# demeter_v25.net
KiCad netlist of a schematic drawn in EAGLE
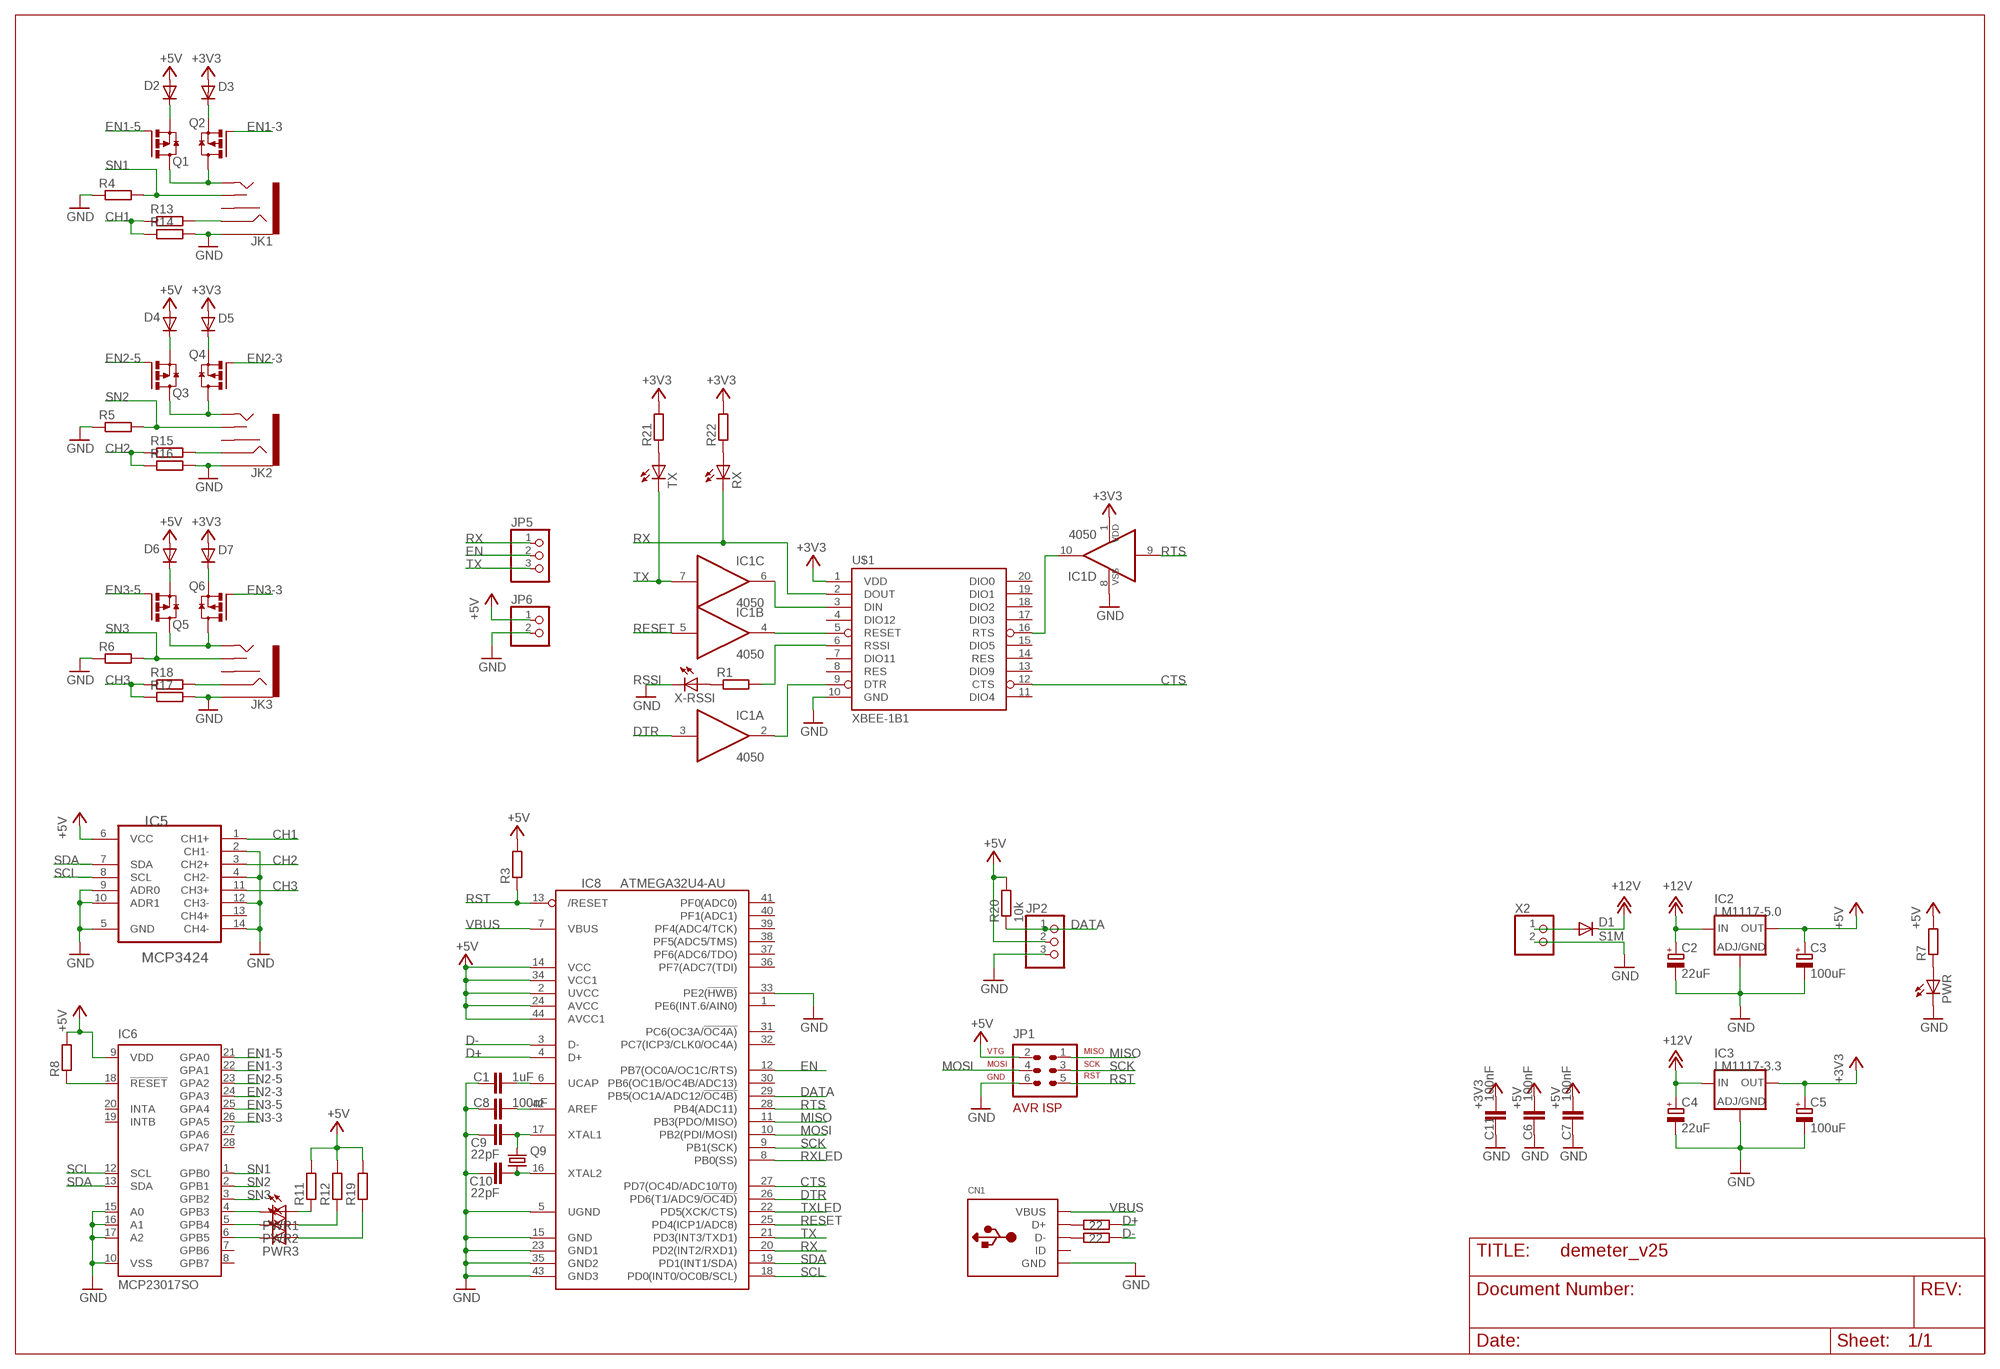
[diagram p0: schematic, sheet 1]

(export (version "E")
  (design (tool "Eeschema 10.0.6"))
  (components
    (comp (ref "C1")
      (value "1uF")
      (footprint "eagle-import:C0805K")
      (libsource (lib "eagle-import") (part "C-EUC0805K"))
    )
    (comp (ref "C2")
      (value "22uF")
      (footprint "eagle-import:PANASONIC_D")
      (libsource (lib "eagle-import") (part "CPOL-EUPD"))
    )
    (comp (ref "C3")
      (value "100uF")
      (footprint "eagle-import:PANASONIC_D")
      (libsource (lib "eagle-import") (part "CPOL-EUPD"))
    )
    (comp (ref "C4")
      (value "22uF")
      (footprint "eagle-import:PANASONIC_D")
      (libsource (lib "eagle-import") (part "CPOL-EUPD"))
    )
    (comp (ref "C5")
      (value "100uF")
      (footprint "eagle-import:PANASONIC_D")
      (libsource (lib "eagle-import") (part "CPOL-EUPD"))
    )
    (comp (ref "C6")
      (value "100nF")
      (footprint "eagle-import:C0805K")
      (libsource (lib "eagle-import") (part "C-EUC0805K"))
    )
    (comp (ref "C7")
      (value "100nF")
      (footprint "eagle-import:C0805K")
      (libsource (lib "eagle-import") (part "C-EUC0805K"))
    )
    (comp (ref "C8")
      (value "100nF")
      (footprint "eagle-import:C0805K")
      (libsource (lib "eagle-import") (part "C-EUC0805K"))
    )
    (comp (ref "C9")
      (value "22pF")
      (footprint "eagle-import:C0805K")
      (libsource (lib "eagle-import") (part "C-EUC0805K"))
    )
    (comp (ref "C10")
      (value "22pF")
      (footprint "eagle-import:C0805K")
      (libsource (lib "eagle-import") (part "C-EUC0805K"))
    )
    (comp (ref "C11")
      (value "100nF")
      (footprint "eagle-import:C0805K")
      (libsource (lib "eagle-import") (part "C-EUC0805K"))
    )
    (comp (ref "CN1")
      (value "USBMINIB")
      (footprint "eagle-import:USB-MINIB")
      (libsource (lib "eagle-import") (part "USBMINIB"))
    )
    (comp (ref "D1")
      (value "S1M")
      (footprint "eagle-import:DO-214AC")
      (libsource (lib "eagle-import") (part "S1M"))
    )
    (comp (ref "D2")
      (value "MBR0520")
      (footprint "eagle-import:SOD123")
      (libsource (lib "eagle-import") (part "MBR0520"))
    )
    (comp (ref "D3")
      (value "MBR0520")
      (footprint "eagle-import:SOD123")
      (libsource (lib "eagle-import") (part "MBR0520"))
    )
    (comp (ref "D4")
      (value "MBR0520")
      (footprint "eagle-import:SOD123")
      (libsource (lib "eagle-import") (part "MBR0520"))
    )
    (comp (ref "D5")
      (value "MBR0520")
      (footprint "eagle-import:SOD123")
      (libsource (lib "eagle-import") (part "MBR0520"))
    )
    (comp (ref "D6")
      (value "MBR0520")
      (footprint "eagle-import:SOD123")
      (libsource (lib "eagle-import") (part "MBR0520"))
    )
    (comp (ref "D7")
      (value "MBR0520")
      (footprint "eagle-import:SOD123")
      (libsource (lib "eagle-import") (part "MBR0520"))
    )
    (comp (ref "IC1")
      (value "4050")
      (footprint "eagle-import:SO16")
      (libsource (lib "eagle-import") (part "4050D"))
    )
    (comp (ref "IC2")
      (value "LM1117-5.0")
      (footprint "eagle-import:DPACK")
      (libsource (lib "eagle-import") (part "LM1117DT"))
    )
    (comp (ref "IC3")
      (value "LM1117-3.3")
      (footprint "eagle-import:DPACK")
      (libsource (lib "eagle-import") (part "LM1117DT"))
    )
    (comp (ref "IC5")
      (value "MCP3424")
      (footprint "eagle-import:SO14")
      (fields (field (name "MPN") "MCP3424-E/SL"))
      (libsource (lib "eagle-import") (part "MCP3424"))
    )
    (comp (ref "IC6")
      (value "MCP23017SO")
      (footprint "eagle-import:SO28W")
      (fields (field (name "MF") "MICROCHIP") (field (name "MPN") "MCP23017-E/SO"))
      (libsource (lib "eagle-import") (part "MCP23017SO"))
    )
    (comp (ref "IC8")
      (value "ATMEGA32U4-AU")
      (footprint "eagle-import:TQFP44")
      (libsource (lib "eagle-import") (part "ATMEGA32U4-AU"))
    )
    (comp (ref "JK1")
      (value "AUDIO-JACK2PTH")
      (footprint "eagle-import:AUDIO-JACK")
      (libsource (lib "eagle-import") (part "AUDIO-JACK2PTH"))
    )
    (comp (ref "JK2")
      (value "AUDIO-JACK2PTH")
      (footprint "eagle-import:AUDIO-JACK")
      (libsource (lib "eagle-import") (part "AUDIO-JACK2PTH"))
    )
    (comp (ref "JK3")
      (value "AUDIO-JACK2PTH")
      (footprint "eagle-import:AUDIO-JACK")
      (libsource (lib "eagle-import") (part "AUDIO-JACK2PTH"))
    )
    (comp (ref "JP1")
      (value "AVR-ISP-6")
      (footprint "eagle-import:AVR-ISP-6")
      (libsource (lib "eagle-import") (part "AVR-ISP-6"))
    )
    (comp (ref "JP2")
      (value "PINHD-1X3180")
      (footprint "eagle-import:1X03")
      (libsource (lib "eagle-import") (part "PINHD-1X3180"))
    )
    (comp (ref "JP5")
      (value "PINHD-1X3180")
      (footprint "eagle-import:1X03")
      (libsource (lib "eagle-import") (part "PINHD-1X3180"))
    )
    (comp (ref "JP6")
      (value "PINHD-1X2")
      (footprint "eagle-import:1X02")
      (libsource (lib "eagle-import") (part "PINHD-1X2"))
    )
    (comp (ref "PWR")
      (value "LED0805")
      (footprint "eagle-import:CHIP-LED0805")
      (libsource (lib "eagle-import") (part "LED0805"))
    )
    (comp (ref "PWR1")
      (value "LED0805")
      (footprint "eagle-import:CHIP-LED0805")
      (libsource (lib "eagle-import") (part "LED0805"))
    )
    (comp (ref "PWR2")
      (value "LED0805")
      (footprint "eagle-import:CHIP-LED0805")
      (libsource (lib "eagle-import") (part "LED0805"))
    )
    (comp (ref "PWR3")
      (value "LED0805")
      (footprint "eagle-import:CHIP-LED0805")
      (libsource (lib "eagle-import") (part "LED0805"))
    )
    (comp (ref "Q1")
      (value "IRLML6402")
      (footprint "eagle-import:SOT23")
      (libsource (lib "eagle-import") (part "IRLML6402"))
    )
    (comp (ref "Q2")
      (value "IRLML6402")
      (footprint "eagle-import:SOT23")
      (libsource (lib "eagle-import") (part "IRLML6402"))
    )
    (comp (ref "Q3")
      (value "IRLML6402")
      (footprint "eagle-import:SOT23")
      (libsource (lib "eagle-import") (part "IRLML6402"))
    )
    (comp (ref "Q4")
      (value "IRLML6402")
      (footprint "eagle-import:SOT23")
      (libsource (lib "eagle-import") (part "IRLML6402"))
    )
    (comp (ref "Q5")
      (value "IRLML6402")
      (footprint "eagle-import:SOT23")
      (libsource (lib "eagle-import") (part "IRLML6402"))
    )
    (comp (ref "Q6")
      (value "IRLML6402")
      (footprint "eagle-import:SOT23")
      (libsource (lib "eagle-import") (part "IRLML6402"))
    )
    (comp (ref "Q9")
      (value "CRYSTALHC49UP")
      (footprint "eagle-import:HC49UP")
      (libsource (lib "eagle-import") (part "CRYSTALHC49UP"))
    )
    (comp (ref "R1")
      (value "R-EU_R0805")
      (footprint "eagle-import:R0805")
      (libsource (lib "eagle-import") (part "R-EU_R0805"))
    )
    (comp (ref "R3")
      (value "R-EU_R0805")
      (footprint "eagle-import:R0805")
      (libsource (lib "eagle-import") (part "R-EU_R0805"))
    )
    (comp (ref "R4")
      (value "R-EU_R0805")
      (footprint "eagle-import:R0805")
      (libsource (lib "eagle-import") (part "R-EU_R0805"))
    )
    (comp (ref "R5")
      (value "R-EU_R0805")
      (footprint "eagle-import:R0805")
      (libsource (lib "eagle-import") (part "R-EU_R0805"))
    )
    (comp (ref "R6")
      (value "R-EU_R0805")
      (footprint "eagle-import:R0805")
      (libsource (lib "eagle-import") (part "R-EU_R0805"))
    )
    (comp (ref "R7")
      (value "R-EU_R0805")
      (footprint "eagle-import:R0805")
      (libsource (lib "eagle-import") (part "R-EU_R0805"))
    )
    (comp (ref "R8")
      (value "R-EU_R0805")
      (footprint "eagle-import:R0805")
      (libsource (lib "eagle-import") (part "R-EU_R0805"))
    )
    (comp (ref "R9")
      (value "22")
      (footprint "eagle-import:R0805")
      (libsource (lib "eagle-import") (part "R-EU_R0805"))
    )
    (comp (ref "R10")
      (value "22")
      (footprint "eagle-import:R0805")
      (libsource (lib "eagle-import") (part "R-EU_R0805"))
    )
    (comp (ref "R11")
      (value "R-EU_R0805")
      (footprint "eagle-import:R0805")
      (libsource (lib "eagle-import") (part "R-EU_R0805"))
    )
    (comp (ref "R12")
      (value "R-EU_R0805")
      (footprint "eagle-import:R0805")
      (libsource (lib "eagle-import") (part "R-EU_R0805"))
    )
    (comp (ref "R13")
      (value "R-EU_R0805")
      (footprint "eagle-import:R0805")
      (libsource (lib "eagle-import") (part "R-EU_R0805"))
    )
    (comp (ref "R14")
      (value "R-EU_R0805")
      (footprint "eagle-import:R0805")
      (libsource (lib "eagle-import") (part "R-EU_R0805"))
    )
    (comp (ref "R15")
      (value "R-EU_R0805")
      (footprint "eagle-import:R0805")
      (libsource (lib "eagle-import") (part "R-EU_R0805"))
    )
    (comp (ref "R16")
      (value "R-EU_R0805")
      (footprint "eagle-import:R0805")
      (libsource (lib "eagle-import") (part "R-EU_R0805"))
    )
    (comp (ref "R17")
      (value "R-EU_R0805")
      (footprint "eagle-import:R0805")
      (libsource (lib "eagle-import") (part "R-EU_R0805"))
    )
    (comp (ref "R18")
      (value "R-EU_R0805")
      (footprint "eagle-import:R0805")
      (libsource (lib "eagle-import") (part "R-EU_R0805"))
    )
    (comp (ref "R19")
      (value "R-EU_R0805")
      (footprint "eagle-import:R0805")
      (libsource (lib "eagle-import") (part "R-EU_R0805"))
    )
    (comp (ref "R20")
      (value "10k")
      (footprint "eagle-import:R0805")
      (libsource (lib "eagle-import") (part "R-EU_R0805"))
    )
    (comp (ref "R21")
      (value "R-EU_R0805")
      (footprint "eagle-import:R0805")
      (libsource (lib "eagle-import") (part "R-EU_R0805"))
    )
    (comp (ref "R22")
      (value "R-EU_R0805")
      (footprint "eagle-import:R0805")
      (libsource (lib "eagle-import") (part "R-EU_R0805"))
    )
    (comp (ref "RX")
      (value "LED0805")
      (footprint "eagle-import:CHIP-LED0805")
      (libsource (lib "eagle-import") (part "LED0805"))
    )
    (comp (ref "TX")
      (value "LED0805")
      (footprint "eagle-import:CHIP-LED0805")
      (libsource (lib "eagle-import") (part "LED0805"))
    )
    (comp (ref "U$1")
      (value "XBEE-1B1")
      (footprint "eagle-import:XBEE-1")
      (libsource (lib "eagle-import") (part "XBEE-1B1"))
    )
    (comp (ref "X-RSSI")
      (value "LED0805")
      (footprint "eagle-import:CHIP-LED0805")
      (libsource (lib "eagle-import") (part "LED0805"))
    )
    (comp (ref "X2")
      (value "W237-102")
      (footprint "eagle-import:W237-102")
      (libsource (lib "eagle-import") (part "W237-102"))
    )
  )
  (nets
    (net (code "1") (name "+3V3") (class "Default")
      (node (ref "C11") (pin "1") (pinfunction "1_1") (pintype "passive"))
      (node (ref "C5") (pin "+") (pinfunction "+_+") (pintype "passive"))
      (node (ref "D3") (pin "A") (pinfunction "A_A") (pintype "passive"))
      (node (ref "D5") (pin "A") (pinfunction "A_A") (pintype "passive"))
      (node (ref "D7") (pin "A") (pinfunction "A_A") (pintype "passive"))
      (node (ref "IC1") (pin "1") (pinfunction "VDD_1") (pintype "power_in"))
      (node (ref "IC3") (pin "4") (pinfunction "OUT_4") (pintype "passive"))
      (node (ref "R21") (pin "2") (pinfunction "2_2") (pintype "passive"))
      (node (ref "R22") (pin "2") (pinfunction "2_2") (pintype "passive"))
      (node (ref "U$1") (pin "1") (pinfunction "VDD_1") (pintype "power_in"))
    )
    (net (code "2") (name "+5V") (class "Default")
      (node (ref "C3") (pin "+") (pinfunction "+_+") (pintype "passive"))
      (node (ref "C6") (pin "1") (pinfunction "1_1") (pintype "passive"))
      (node (ref "C7") (pin "1") (pinfunction "1_1") (pintype "passive"))
      (node (ref "D2") (pin "A") (pinfunction "A_A") (pintype "passive"))
      (node (ref "D4") (pin "A") (pinfunction "A_A") (pintype "passive"))
      (node (ref "D6") (pin "A") (pinfunction "A_A") (pintype "passive"))
      (node (ref "IC2") (pin "4") (pinfunction "OUT_4") (pintype "passive"))
      (node (ref "IC5") (pin "6") (pinfunction "VCC_6") (pintype "power_in"))
      (node (ref "IC6") (pin "9") (pinfunction "VDD_9") (pintype "power_in"))
      (node (ref "IC8") (pin "14") (pinfunction "VCC_14") (pintype "bidirectional"))
      (node (ref "IC8") (pin "2") (pinfunction "UVCC_2") (pintype "bidirectional"))
      (node (ref "IC8") (pin "24") (pinfunction "AVCC_24") (pintype "bidirectional"))
      (node (ref "IC8") (pin "34") (pinfunction "VCC1_34") (pintype "bidirectional"))
      (node (ref "IC8") (pin "44") (pinfunction "AVCC1_44") (pintype "bidirectional"))
      (node (ref "JP1") (pin "2") (pinfunction "VTG_2") (pintype "passive"))
      (node (ref "JP2") (pin "2") (pinfunction "2_2") (pintype "passive"))
      (node (ref "JP6") (pin "1") (pinfunction "1_1") (pintype "passive"))
      (node (ref "R11") (pin "2") (pinfunction "2_2") (pintype "passive"))
      (node (ref "R12") (pin "2") (pinfunction "2_2") (pintype "passive"))
      (node (ref "R19") (pin "2") (pinfunction "2_2") (pintype "passive"))
      (node (ref "R20") (pin "2") (pinfunction "2_2") (pintype "passive"))
      (node (ref "R3") (pin "2") (pinfunction "2_2") (pintype "passive"))
      (node (ref "R7") (pin "2") (pinfunction "2_2") (pintype "passive"))
      (node (ref "R8") (pin "2") (pinfunction "2_2") (pintype "passive"))
    )
    (net (code "3") (name "+12V") (class "Default")
      (node (ref "C2") (pin "+") (pinfunction "+_+") (pintype "passive"))
      (node (ref "C4") (pin "+") (pinfunction "+_+") (pintype "passive"))
      (node (ref "D1") (pin "C") (pinfunction "C_C") (pintype "passive"))
      (node (ref "IC2") (pin "3") (pinfunction "IN_3") (pintype "input"))
      (node (ref "IC3") (pin "3") (pinfunction "IN_3") (pintype "input"))
    )
    (net (code "4") (name "/CH1") (class "Default")
      (node (ref "IC5") (pin "1") (pinfunction "CH1+_1") (pintype "input"))
      (node (ref "R13") (pin "1") (pinfunction "1_1") (pintype "passive"))
      (node (ref "R14") (pin "1") (pinfunction "1_1") (pintype "passive"))
    )
    (net (code "5") (name "/CH2") (class "Default")
      (node (ref "IC5") (pin "3") (pinfunction "CH2+_3") (pintype "input"))
      (node (ref "R15") (pin "1") (pinfunction "1_1") (pintype "passive"))
      (node (ref "R16") (pin "1") (pinfunction "1_1") (pintype "passive"))
    )
    (net (code "6") (name "/CH3") (class "Default")
      (node (ref "IC5") (pin "11") (pinfunction "CH3+_11") (pintype "input"))
      (node (ref "R17") (pin "1") (pinfunction "1_1") (pintype "passive"))
      (node (ref "R18") (pin "1") (pinfunction "1_1") (pintype "passive"))
    )
    (net (code "7") (name "/CTS") (class "Default")
      (node (ref "IC8") (pin "27") (pinfunction "PD7(OC4D/ADC10/T0)_27") (pintype "bidirectional"))
      (node (ref "U$1") (pin "12") (pinfunction "CTS_12") (pintype "output"))
    )
    (net (code "8") (name "/D+") (class "Default")
      (node (ref "IC8") (pin "4") (pinfunction "D+_4") (pintype "bidirectional"))
      (node (ref "R9") (pin "1") (pinfunction "1_1") (pintype "passive"))
    )
    (net (code "9") (name "/D-") (class "Default")
      (node (ref "IC8") (pin "3") (pinfunction "D-_3") (pintype "bidirectional"))
      (node (ref "R10") (pin "1") (pinfunction "1_1") (pintype "passive"))
    )
    (net (code "10") (name "/DATA") (class "Default")
      (node (ref "IC8") (pin "29") (pinfunction "PB5(OC1A/ADC12/~{OC4B})_29") (pintype "bidirectional"))
      (node (ref "JP2") (pin "1") (pinfunction "1_1") (pintype "passive"))
      (node (ref "R20") (pin "1") (pinfunction "1_1") (pintype "passive"))
    )
    (net (code "11") (name "/DTR") (class "Default")
      (node (ref "IC1") (pin "3") (pinfunction "I_3") (pintype "input"))
      (node (ref "IC8") (pin "26") (pinfunction "PD6(T1/ADC9/~{OC4D})_26") (pintype "bidirectional"))
    )
    (net (code "12") (name "/EN") (class "Default")
      (node (ref "IC8") (pin "12") (pinfunction "PB7(OC0A/OC1C/RTS)_12") (pintype "bidirectional"))
      (node (ref "JP5") (pin "2") (pinfunction "2_2") (pintype "passive"))
    )
    (net (code "13") (name "/EN1-3") (class "Default")
      (node (ref "IC6") (pin "22") (pinfunction "GPA1_22") (pintype "bidirectional"))
      (node (ref "Q2") (pin "1") (pinfunction "G_1") (pintype "passive"))
    )
    (net (code "14") (name "/EN1-5") (class "Default")
      (node (ref "IC6") (pin "21") (pinfunction "GPA0_21") (pintype "bidirectional"))
      (node (ref "Q1") (pin "1") (pinfunction "G_1") (pintype "passive"))
    )
    (net (code "15") (name "/EN2-3") (class "Default")
      (node (ref "IC6") (pin "24") (pinfunction "GPA3_24") (pintype "bidirectional"))
      (node (ref "Q4") (pin "1") (pinfunction "G_1") (pintype "passive"))
    )
    (net (code "16") (name "/EN2-5") (class "Default")
      (node (ref "IC6") (pin "23") (pinfunction "GPA2_23") (pintype "bidirectional"))
      (node (ref "Q3") (pin "1") (pinfunction "G_1") (pintype "passive"))
    )
    (net (code "17") (name "/EN3-3") (class "Default")
      (node (ref "IC6") (pin "26") (pinfunction "GPA5_26") (pintype "bidirectional"))
      (node (ref "Q6") (pin "1") (pinfunction "G_1") (pintype "passive"))
    )
    (net (code "18") (name "/EN3-5") (class "Default")
      (node (ref "IC6") (pin "25") (pinfunction "GPA4_25") (pintype "bidirectional"))
      (node (ref "Q5") (pin "1") (pinfunction "G_1") (pintype "passive"))
    )
    (net (code "19") (name "/MISO") (class "Default")
      (node (ref "IC8") (pin "11") (pinfunction "PB3(PDO/MISO)_11") (pintype "bidirectional"))
      (node (ref "JP1") (pin "1") (pinfunction "MISO_1") (pintype "passive"))
    )
    (net (code "20") (name "/MOSI") (class "Default")
      (node (ref "IC8") (pin "10") (pinfunction "PB2(PDI/MOSI)_10") (pintype "bidirectional"))
      (node (ref "JP1") (pin "4") (pinfunction "MOSI_4") (pintype "passive"))
    )
    (net (code "21") (name "/RESET") (class "Default")
      (node (ref "IC1") (pin "5") (pinfunction "I_5") (pintype "input"))
      (node (ref "IC8") (pin "25") (pinfunction "PD4(ICP1/ADC8)_25") (pintype "bidirectional"))
    )
    (net (code "22") (name "/RSSI") (class "Default")
      (node (ref "R1") (pin "2") (pinfunction "2_2") (pintype "passive"))
      (node (ref "U$1") (pin "6") (pinfunction "RSSI_6") (pintype "bidirectional"))
    )
    (net (code "23") (name "/RST") (class "Default")
      (node (ref "IC8") (pin "13") (pinfunction "/RESET_13") (pintype "bidirectional"))
      (node (ref "JP1") (pin "5") (pinfunction "RST_5") (pintype "passive"))
      (node (ref "R3") (pin "1") (pinfunction "1_1") (pintype "passive"))
    )
    (net (code "24") (name "/RTS") (class "Default")
      (node (ref "IC1") (pin "9") (pinfunction "I_9") (pintype "input"))
      (node (ref "IC8") (pin "28") (pinfunction "PB4(ADC11)_28") (pintype "bidirectional"))
    )
    (net (code "25") (name "/RX") (class "Default")
      (node (ref "IC8") (pin "20") (pinfunction "PD2(INT2/RXD1)_20") (pintype "bidirectional"))
      (node (ref "JP5") (pin "1") (pinfunction "1_1") (pintype "passive"))
      (node (ref "RX") (pin "C") (pinfunction "C_C") (pintype "passive"))
      (node (ref "U$1") (pin "2") (pinfunction "DOUT_2") (pintype "output"))
    )
    (net (code "26") (name "/RXLED") (class "Default")
      (node (ref "IC8") (pin "8") (pinfunction "PB0(SS)_8") (pintype "bidirectional"))
    )
    (net (code "27") (name "/SCK") (class "Default")
      (node (ref "IC8") (pin "9") (pinfunction "PB1(SCK)_9") (pintype "bidirectional"))
      (node (ref "JP1") (pin "3") (pinfunction "SCK_3") (pintype "passive"))
    )
    (net (code "28") (name "/SCL") (class "Default")
      (node (ref "IC5") (pin "8") (pinfunction "SCL_8") (pintype "input"))
      (node (ref "IC6") (pin "12") (pinfunction "SCL_12") (pintype "input"))
      (node (ref "IC8") (pin "18") (pinfunction "PD0(INT0/OC0B/SCL)_18") (pintype "bidirectional"))
    )
    (net (code "29") (name "/SDA") (class "Default")
      (node (ref "IC5") (pin "7") (pinfunction "SDA_7") (pintype "bidirectional"))
      (node (ref "IC6") (pin "13") (pinfunction "SDA_13") (pintype "bidirectional"))
      (node (ref "IC8") (pin "19") (pinfunction "PD1(INT1/SDA)_19") (pintype "bidirectional"))
    )
    (net (code "30") (name "/SN1") (class "Default")
      (node (ref "IC6") (pin "1") (pinfunction "GPB0_1") (pintype "bidirectional"))
      (node (ref "JK1") (pin "TSH") (pinfunction "TSH_TSH") (pintype "bidirectional"))
      (node (ref "R4") (pin "2") (pinfunction "2_2") (pintype "passive"))
    )
    (net (code "31") (name "/SN2") (class "Default")
      (node (ref "IC6") (pin "2") (pinfunction "GPB1_2") (pintype "bidirectional"))
      (node (ref "JK2") (pin "TSH") (pinfunction "TSH_TSH") (pintype "bidirectional"))
      (node (ref "R5") (pin "2") (pinfunction "2_2") (pintype "passive"))
    )
    (net (code "32") (name "/SN3") (class "Default")
      (node (ref "IC6") (pin "3") (pinfunction "GPB2_3") (pintype "bidirectional"))
      (node (ref "JK3") (pin "TSH") (pinfunction "TSH_TSH") (pintype "bidirectional"))
      (node (ref "R6") (pin "2") (pinfunction "2_2") (pintype "passive"))
    )
    (net (code "33") (name "/TX") (class "Default")
      (node (ref "IC1") (pin "7") (pinfunction "I_7") (pintype "input"))
      (node (ref "IC8") (pin "21") (pinfunction "PD3(INT3/TXD1)_21") (pintype "bidirectional"))
      (node (ref "JP5") (pin "3") (pinfunction "3_3") (pintype "passive"))
      (node (ref "TX") (pin "C") (pinfunction "C_C") (pintype "passive"))
    )
    (net (code "34") (name "/TXLED") (class "Default")
      (node (ref "IC8") (pin "22") (pinfunction "PD5(XCK/CTS)_22") (pintype "bidirectional"))
    )
    (net (code "35") (name "/VBUS") (class "Default")
      (node (ref "CN1") (pin "VBUS") (pinfunction "VBUS_VBUS") (pintype "power_in"))
      (node (ref "IC8") (pin "7") (pinfunction "VBUS_7") (pintype "bidirectional"))
    )
    (net (code "36") (name "GND") (class "Default")
      (node (ref "C1") (pin "2") (pinfunction "2_2") (pintype "passive"))
      (node (ref "C10") (pin "2") (pinfunction "2_2") (pintype "passive"))
      (node (ref "C11") (pin "2") (pinfunction "2_2") (pintype "passive"))
      (node (ref "C2") (pin "-") (pinfunction "-_-") (pintype "passive"))
      (node (ref "C3") (pin "-") (pinfunction "-_-") (pintype "passive"))
      (node (ref "C4") (pin "-") (pinfunction "-_-") (pintype "passive"))
      (node (ref "C5") (pin "-") (pinfunction "-_-") (pintype "passive"))
      (node (ref "C6") (pin "2") (pinfunction "2_2") (pintype "passive"))
      (node (ref "C7") (pin "2") (pinfunction "2_2") (pintype "passive"))
      (node (ref "C8") (pin "2") (pinfunction "2_2") (pintype "passive"))
      (node (ref "C9") (pin "2") (pinfunction "2_2") (pintype "passive"))
      (node (ref "CN1") (pin "GND") (pinfunction "GND_GND") (pintype "power_in"))
      (node (ref "IC1") (pin "8") (pinfunction "VSS_8") (pintype "power_in"))
      (node (ref "IC2") (pin "1") (pinfunction "ADJ_1") (pintype "input"))
      (node (ref "IC3") (pin "1") (pinfunction "ADJ_1") (pintype "input"))
      (node (ref "IC5") (pin "10") (pinfunction "ADR1_10") (pintype "input"))
      (node (ref "IC5") (pin "12") (pinfunction "CH3-_12") (pintype "input"))
      (node (ref "IC5") (pin "14") (pinfunction "CH4-_14") (pintype "input"))
      (node (ref "IC5") (pin "2") (pinfunction "CH1-_2") (pintype "input"))
      (node (ref "IC5") (pin "4") (pinfunction "CH2-_4") (pintype "input"))
      (node (ref "IC5") (pin "5") (pinfunction "GND_5") (pintype "power_in"))
      (node (ref "IC5") (pin "9") (pinfunction "ADR0_9") (pintype "input"))
      (node (ref "IC6") (pin "10") (pinfunction "VSS_10") (pintype "power_in"))
      (node (ref "IC6") (pin "15") (pinfunction "A0_15") (pintype "input"))
      (node (ref "IC6") (pin "16") (pinfunction "A1_16") (pintype "input"))
      (node (ref "IC6") (pin "17") (pinfunction "A2_17") (pintype "input"))
      (node (ref "IC8") (pin "15") (pinfunction "GND_15") (pintype "bidirectional"))
      (node (ref "IC8") (pin "23") (pinfunction "GND1_23") (pintype "bidirectional"))
      (node (ref "IC8") (pin "33") (pinfunction "PE2(~{HWB})_33") (pintype "bidirectional"))
      (node (ref "IC8") (pin "35") (pinfunction "GND2_35") (pintype "bidirectional"))
      (node (ref "IC8") (pin "43") (pinfunction "GND3_43") (pintype "bidirectional"))
      (node (ref "IC8") (pin "5") (pinfunction "UGND_5") (pintype "bidirectional"))
      (node (ref "JK1") (pin "SLEEVE") (pinfunction "SLEEVE_SLEEVE") (pintype "bidirectional"))
      (node (ref "JK2") (pin "SLEEVE") (pinfunction "SLEEVE_SLEEVE") (pintype "bidirectional"))
      (node (ref "JK3") (pin "SLEEVE") (pinfunction "SLEEVE_SLEEVE") (pintype "bidirectional"))
      (node (ref "JP1") (pin "6") (pinfunction "GND_6") (pintype "passive"))
      (node (ref "JP2") (pin "3") (pinfunction "3_3") (pintype "passive"))
      (node (ref "JP6") (pin "2") (pinfunction "2_2") (pintype "passive"))
      (node (ref "PWR") (pin "C") (pinfunction "C_C") (pintype "passive"))
      (node (ref "R14") (pin "2") (pinfunction "2_2") (pintype "passive"))
      (node (ref "R16") (pin "2") (pinfunction "2_2") (pintype "passive"))
      (node (ref "R17") (pin "2") (pinfunction "2_2") (pintype "passive"))
      (node (ref "R4") (pin "1") (pinfunction "1_1") (pintype "passive"))
      (node (ref "R5") (pin "1") (pinfunction "1_1") (pintype "passive"))
      (node (ref "R6") (pin "1") (pinfunction "1_1") (pintype "passive"))
      (node (ref "U$1") (pin "10") (pinfunction "GND_10") (pintype "power_in"))
      (node (ref "X-RSSI") (pin "C") (pinfunction "C_C") (pintype "passive"))
      (node (ref "X2") (pin "2") (pinfunction "2_2") (pintype "passive"))
    )
    (net (code "37") (name "Net-(CN1-PadD+)") (class "Default")
      (node (ref "CN1") (pin "D+") (pinfunction "D+_D+") (pintype "bidirectional"))
      (node (ref "R9") (pin "2") (pinfunction "2_2") (pintype "passive"))
    )
    (net (code "38") (name "Net-(CN1-PadD-)") (class "Default")
      (node (ref "CN1") (pin "D-") (pinfunction "D-_D-") (pintype "bidirectional"))
      (node (ref "R10") (pin "2") (pinfunction "2_2") (pintype "passive"))
    )
    (net (code "39") (name "Net-(D1-PadA)") (class "Default")
      (node (ref "D1") (pin "A") (pinfunction "A_A") (pintype "passive"))
      (node (ref "X2") (pin "1") (pinfunction "1_1") (pintype "passive"))
    )
    (net (code "40") (name "Net-(IC1A-O)") (class "Default")
      (node (ref "IC1") (pin "2") (pinfunction "O_2") (pintype "output"))
      (node (ref "U$1") (pin "9") (pinfunction "DTR_9") (pintype "bidirectional"))
    )
    (net (code "41") (name "Net-(IC1B-O)") (class "Default")
      (node (ref "IC1") (pin "4") (pinfunction "O_4") (pintype "output"))
      (node (ref "U$1") (pin "5") (pinfunction "RESET_5") (pintype "input"))
    )
    (net (code "42") (name "Net-(IC1C-O)") (class "Default")
      (node (ref "IC1") (pin "6") (pinfunction "O_6") (pintype "output"))
      (node (ref "U$1") (pin "3") (pinfunction "DIN_3") (pintype "input"))
    )
    (net (code "43") (name "Net-(IC1D-O)") (class "Default")
      (node (ref "IC1") (pin "10") (pinfunction "O_10") (pintype "output"))
      (node (ref "U$1") (pin "16") (pinfunction "RTS_16") (pintype "input"))
    )
    (net (code "44") (name "Net-(IC6-GPB3)") (class "Default")
      (node (ref "IC6") (pin "4") (pinfunction "GPB3_4") (pintype "bidirectional"))
      (node (ref "PWR1") (pin "C") (pinfunction "C_C") (pintype "passive"))
    )
    (net (code "45") (name "Net-(IC6-GPB4)") (class "Default")
      (node (ref "IC6") (pin "5") (pinfunction "GPB4_5") (pintype "bidirectional"))
      (node (ref "PWR2") (pin "C") (pinfunction "C_C") (pintype "passive"))
    )
    (net (code "46") (name "Net-(IC6-GPB5)") (class "Default")
      (node (ref "IC6") (pin "6") (pinfunction "GPB5_6") (pintype "bidirectional"))
      (node (ref "PWR3") (pin "C") (pinfunction "C_C") (pintype "passive"))
    )
    (net (code "47") (name "Net-(IC6-~{RESET})") (class "Default")
      (node (ref "IC6") (pin "18") (pinfunction "~{RESET}_18") (pintype "input"))
      (node (ref "R8") (pin "1") (pinfunction "1_1") (pintype "passive"))
    )
    (net (code "48") (name "Net-(IC8-AREF)") (class "Default")
      (node (ref "C8") (pin "1") (pinfunction "1_1") (pintype "passive"))
      (node (ref "IC8") (pin "42") (pinfunction "AREF_42") (pintype "bidirectional"))
    )
    (net (code "49") (name "Net-(IC8-UCAP)") (class "Default")
      (node (ref "C1") (pin "1") (pinfunction "1_1") (pintype "passive"))
      (node (ref "IC8") (pin "6") (pinfunction "UCAP_6") (pintype "bidirectional"))
    )
    (net (code "50") (name "Net-(IC8-XTAL1)") (class "Default")
      (node (ref "C9") (pin "1") (pinfunction "1_1") (pintype "passive"))
      (node (ref "IC8") (pin "17") (pinfunction "XTAL1_17") (pintype "bidirectional"))
      (node (ref "Q9") (pin "2") (pinfunction "2_2") (pintype "passive"))
    )
    (net (code "51") (name "Net-(IC8-XTAL2)") (class "Default")
      (node (ref "C10") (pin "1") (pinfunction "1_1") (pintype "passive"))
      (node (ref "IC8") (pin "16") (pinfunction "XTAL2_16") (pintype "bidirectional"))
      (node (ref "Q9") (pin "1") (pinfunction "1_1") (pintype "passive"))
    )
    (net (code "52") (name "Net-(JK1-PadRING)") (class "Default")
      (node (ref "JK1") (pin "RING") (pinfunction "RING_RING") (pintype "bidirectional"))
      (node (ref "R13") (pin "2") (pinfunction "2_2") (pintype "passive"))
    )
    (net (code "53") (name "Net-(JK2-PadRING)") (class "Default")
      (node (ref "JK2") (pin "RING") (pinfunction "RING_RING") (pintype "bidirectional"))
      (node (ref "R15") (pin "2") (pinfunction "2_2") (pintype "passive"))
    )
    (net (code "54") (name "Net-(JK3-PadRING)") (class "Default")
      (node (ref "JK3") (pin "RING") (pinfunction "RING_RING") (pintype "bidirectional"))
      (node (ref "R18") (pin "2") (pinfunction "2_2") (pintype "passive"))
    )
    (net (code "55") (name "Net-(PWR-PadA)") (class "Default")
      (node (ref "PWR") (pin "A") (pinfunction "A_A") (pintype "passive"))
      (node (ref "R7") (pin "1") (pinfunction "1_1") (pintype "passive"))
    )
    (net (code "56") (name "Net-(PWR1-PadA)") (class "Default")
      (node (ref "PWR1") (pin "A") (pinfunction "A_A") (pintype "passive"))
      (node (ref "R11") (pin "1") (pinfunction "1_1") (pintype "passive"))
    )
    (net (code "57") (name "Net-(PWR2-PadA)") (class "Default")
      (node (ref "PWR2") (pin "A") (pinfunction "A_A") (pintype "passive"))
      (node (ref "R12") (pin "1") (pinfunction "1_1") (pintype "passive"))
    )
    (net (code "58") (name "Net-(PWR3-PadA)") (class "Default")
      (node (ref "PWR3") (pin "A") (pinfunction "A_A") (pintype "passive"))
      (node (ref "R19") (pin "1") (pinfunction "1_1") (pintype "passive"))
    )
    (net (code "59") (name "Net-(Q1-D)") (class "Default")
      (node (ref "JK1") (pin "TIP") (pinfunction "TIP_TIP") (pintype "bidirectional"))
      (node (ref "Q1") (pin "3") (pinfunction "D_3") (pintype "passive"))
      (node (ref "Q2") (pin "3") (pinfunction "D_3") (pintype "passive"))
    )
    (net (code "60") (name "Net-(Q1-S)") (class "Default")
      (node (ref "D2") (pin "C") (pinfunction "C_C") (pintype "passive"))
      (node (ref "Q1") (pin "2") (pinfunction "S_2") (pintype "passive"))
    )
    (net (code "61") (name "Net-(Q2-S)") (class "Default")
      (node (ref "D3") (pin "C") (pinfunction "C_C") (pintype "passive"))
      (node (ref "Q2") (pin "2") (pinfunction "S_2") (pintype "passive"))
    )
    (net (code "62") (name "Net-(Q3-D)") (class "Default")
      (node (ref "JK2") (pin "TIP") (pinfunction "TIP_TIP") (pintype "bidirectional"))
      (node (ref "Q3") (pin "3") (pinfunction "D_3") (pintype "passive"))
      (node (ref "Q4") (pin "3") (pinfunction "D_3") (pintype "passive"))
    )
    (net (code "63") (name "Net-(Q3-S)") (class "Default")
      (node (ref "D4") (pin "C") (pinfunction "C_C") (pintype "passive"))
      (node (ref "Q3") (pin "2") (pinfunction "S_2") (pintype "passive"))
    )
    (net (code "64") (name "Net-(Q4-S)") (class "Default")
      (node (ref "D5") (pin "C") (pinfunction "C_C") (pintype "passive"))
      (node (ref "Q4") (pin "2") (pinfunction "S_2") (pintype "passive"))
    )
    (net (code "65") (name "Net-(Q5-D)") (class "Default")
      (node (ref "JK3") (pin "TIP") (pinfunction "TIP_TIP") (pintype "bidirectional"))
      (node (ref "Q5") (pin "3") (pinfunction "D_3") (pintype "passive"))
      (node (ref "Q6") (pin "3") (pinfunction "D_3") (pintype "passive"))
    )
    (net (code "66") (name "Net-(Q5-S)") (class "Default")
      (node (ref "D6") (pin "C") (pinfunction "C_C") (pintype "passive"))
      (node (ref "Q5") (pin "2") (pinfunction "S_2") (pintype "passive"))
    )
    (net (code "67") (name "Net-(Q6-S)") (class "Default")
      (node (ref "D7") (pin "C") (pinfunction "C_C") (pintype "passive"))
      (node (ref "Q6") (pin "2") (pinfunction "S_2") (pintype "passive"))
    )
    (net (code "68") (name "Net-(R1-Pad1)") (class "Default")
      (node (ref "R1") (pin "1") (pinfunction "1_1") (pintype "passive"))
      (node (ref "X-RSSI") (pin "A") (pinfunction "A_A") (pintype "passive"))
    )
    (net (code "69") (name "Net-(R21-Pad1)") (class "Default")
      (node (ref "R21") (pin "1") (pinfunction "1_1") (pintype "passive"))
      (node (ref "TX") (pin "A") (pinfunction "A_A") (pintype "passive"))
    )
    (net (code "70") (name "Net-(R22-Pad1)") (class "Default")
      (node (ref "R22") (pin "1") (pinfunction "1_1") (pintype "passive"))
      (node (ref "RX") (pin "A") (pinfunction "A_A") (pintype "passive"))
    )
    (net (code "71") (name "unconnected-(CN1-PadID)") (class "Default")
      (node (ref "CN1") (pin "ID") (pinfunction "ID_ID") (pintype "bidirectional"))
    )
    (net (code "72") (name "unconnected-(IC5-CH4+-Pad13)") (class "Default")
      (node (ref "IC5") (pin "13") (pinfunction "CH4+_13") (pintype "input"))
    )
    (net (code "73") (name "unconnected-(IC6-GPA6-Pad27)") (class "Default")
      (node (ref "IC6") (pin "27") (pinfunction "GPA6_27") (pintype "bidirectional"))
    )
    (net (code "74") (name "unconnected-(IC6-GPA7-Pad28)") (class "Default")
      (node (ref "IC6") (pin "28") (pinfunction "GPA7_28") (pintype "bidirectional"))
    )
    (net (code "75") (name "unconnected-(IC6-GPB6-Pad7)") (class "Default")
      (node (ref "IC6") (pin "7") (pinfunction "GPB6_7") (pintype "bidirectional"))
    )
    (net (code "76") (name "unconnected-(IC6-GPB7-Pad8)") (class "Default")
      (node (ref "IC6") (pin "8") (pinfunction "GPB7_8") (pintype "bidirectional"))
    )
    (net (code "77") (name "unconnected-(IC6-INTA-Pad20)") (class "Default")
      (node (ref "IC6") (pin "20") (pinfunction "INTA_20") (pintype "output"))
    )
    (net (code "78") (name "unconnected-(IC6-INTB-Pad19)") (class "Default")
      (node (ref "IC6") (pin "19") (pinfunction "INTB_19") (pintype "output"))
    )
    (net (code "79") (name "unconnected-(IC8-PB6(OC1B{slash}OC4B{slash}ADC13)-Pad30)") (class "Default")
      (node (ref "IC8") (pin "30") (pinfunction "PB6(OC1B/OC4B/ADC13)_30") (pintype "bidirectional"))
    )
    (net (code "80") (name "unconnected-(IC8-PC6(OC3A{slash}~{OC4A})-Pad31)") (class "Default")
      (node (ref "IC8") (pin "31") (pinfunction "PC6(OC3A/~{OC4A})_31") (pintype "bidirectional"))
    )
    (net (code "81") (name "unconnected-(IC8-PC7(ICP3{slash}CLK0{slash}OC4A)-Pad32)") (class "Default")
      (node (ref "IC8") (pin "32") (pinfunction "PC7(ICP3/CLK0/OC4A)_32") (pintype "bidirectional"))
    )
    (net (code "82") (name "unconnected-(IC8-PE6(INT.6{slash}AIN0)-Pad1)") (class "Default")
      (node (ref "IC8") (pin "1") (pinfunction "PE6(INT.6/AIN0)_1") (pintype "bidirectional"))
    )
    (net (code "83") (name "unconnected-(IC8-PF0(ADC0)-Pad41)") (class "Default")
      (node (ref "IC8") (pin "41") (pinfunction "PF0(ADC0)_41") (pintype "bidirectional"))
    )
    (net (code "84") (name "unconnected-(IC8-PF1(ADC1)-Pad40)") (class "Default")
      (node (ref "IC8") (pin "40") (pinfunction "PF1(ADC1)_40") (pintype "bidirectional"))
    )
    (net (code "85") (name "unconnected-(IC8-PF4(ADC4{slash}TCK)-Pad39)") (class "Default")
      (node (ref "IC8") (pin "39") (pinfunction "PF4(ADC4/TCK)_39") (pintype "bidirectional"))
    )
    (net (code "86") (name "unconnected-(IC8-PF5(ADC5{slash}TMS)-Pad38)") (class "Default")
      (node (ref "IC8") (pin "38") (pinfunction "PF5(ADC5/TMS)_38") (pintype "bidirectional"))
    )
    (net (code "87") (name "unconnected-(IC8-PF6(ADC6{slash}TDO)-Pad37)") (class "Default")
      (node (ref "IC8") (pin "37") (pinfunction "PF6(ADC6/TDO)_37") (pintype "bidirectional"))
    )
    (net (code "88") (name "unconnected-(IC8-PF7(ADC7(TDI)-Pad36)") (class "Default")
      (node (ref "IC8") (pin "36") (pinfunction "PF7(ADC7(TDI)_36") (pintype "bidirectional"))
    )
    (net (code "89") (name "unconnected-(JK1-PadRSH)") (class "Default")
      (node (ref "JK1") (pin "RSH") (pinfunction "RSH_RSH") (pintype "bidirectional"))
    )
    (net (code "90") (name "unconnected-(JK2-PadRSH)") (class "Default")
      (node (ref "JK2") (pin "RSH") (pinfunction "RSH_RSH") (pintype "bidirectional"))
    )
    (net (code "91") (name "unconnected-(JK3-PadRSH)") (class "Default")
      (node (ref "JK3") (pin "RSH") (pinfunction "RSH_RSH") (pintype "bidirectional"))
    )
    (net (code "92") (name "unconnected-(U$1-DIO0-Pad20)") (class "Default")
      (node (ref "U$1") (pin "20") (pinfunction "DIO0_20") (pintype "bidirectional"))
    )
    (net (code "93") (name "unconnected-(U$1-DIO1-Pad19)") (class "Default")
      (node (ref "U$1") (pin "19") (pinfunction "DIO1_19") (pintype "bidirectional"))
    )
    (net (code "94") (name "unconnected-(U$1-DIO2-Pad18)") (class "Default")
      (node (ref "U$1") (pin "18") (pinfunction "DIO2_18") (pintype "bidirectional"))
    )
    (net (code "95") (name "unconnected-(U$1-DIO3-Pad17)") (class "Default")
      (node (ref "U$1") (pin "17") (pinfunction "DIO3_17") (pintype "bidirectional"))
    )
    (net (code "96") (name "unconnected-(U$1-DIO4-Pad11)") (class "Default")
      (node (ref "U$1") (pin "11") (pinfunction "DIO4_11") (pintype "bidirectional"))
    )
    (net (code "97") (name "unconnected-(U$1-DIO5-Pad15)") (class "Default")
      (node (ref "U$1") (pin "15") (pinfunction "DIO5_15") (pintype "bidirectional"))
    )
    (net (code "98") (name "unconnected-(U$1-DIO9-Pad13)") (class "Default")
      (node (ref "U$1") (pin "13") (pinfunction "DIO9_13") (pintype "bidirectional"))
    )
    (net (code "99") (name "unconnected-(U$1-DIO11-Pad7)") (class "Default")
      (node (ref "U$1") (pin "7") (pinfunction "DIO11_7") (pintype "bidirectional"))
    )
    (net (code "100") (name "unconnected-(U$1-DIO12-Pad4)") (class "Default")
      (node (ref "U$1") (pin "4") (pinfunction "DIO12_4") (pintype "bidirectional"))
    )
    (net (code "101") (name "unconnected-(U$1-RES-Pad8)") (class "Default")
      (node (ref "U$1") (pin "8") (pinfunction "RES_8") (pintype "bidirectional"))
    )
    (net (code "102") (name "unconnected-(U$1-RES-Pad14)") (class "Default")
      (node (ref "U$1") (pin "14") (pinfunction "RES_14") (pintype "bidirectional"))
    )
  )
)
